# PCB_v2.net
KiCad netlist of a schematic drawn in EAGLE
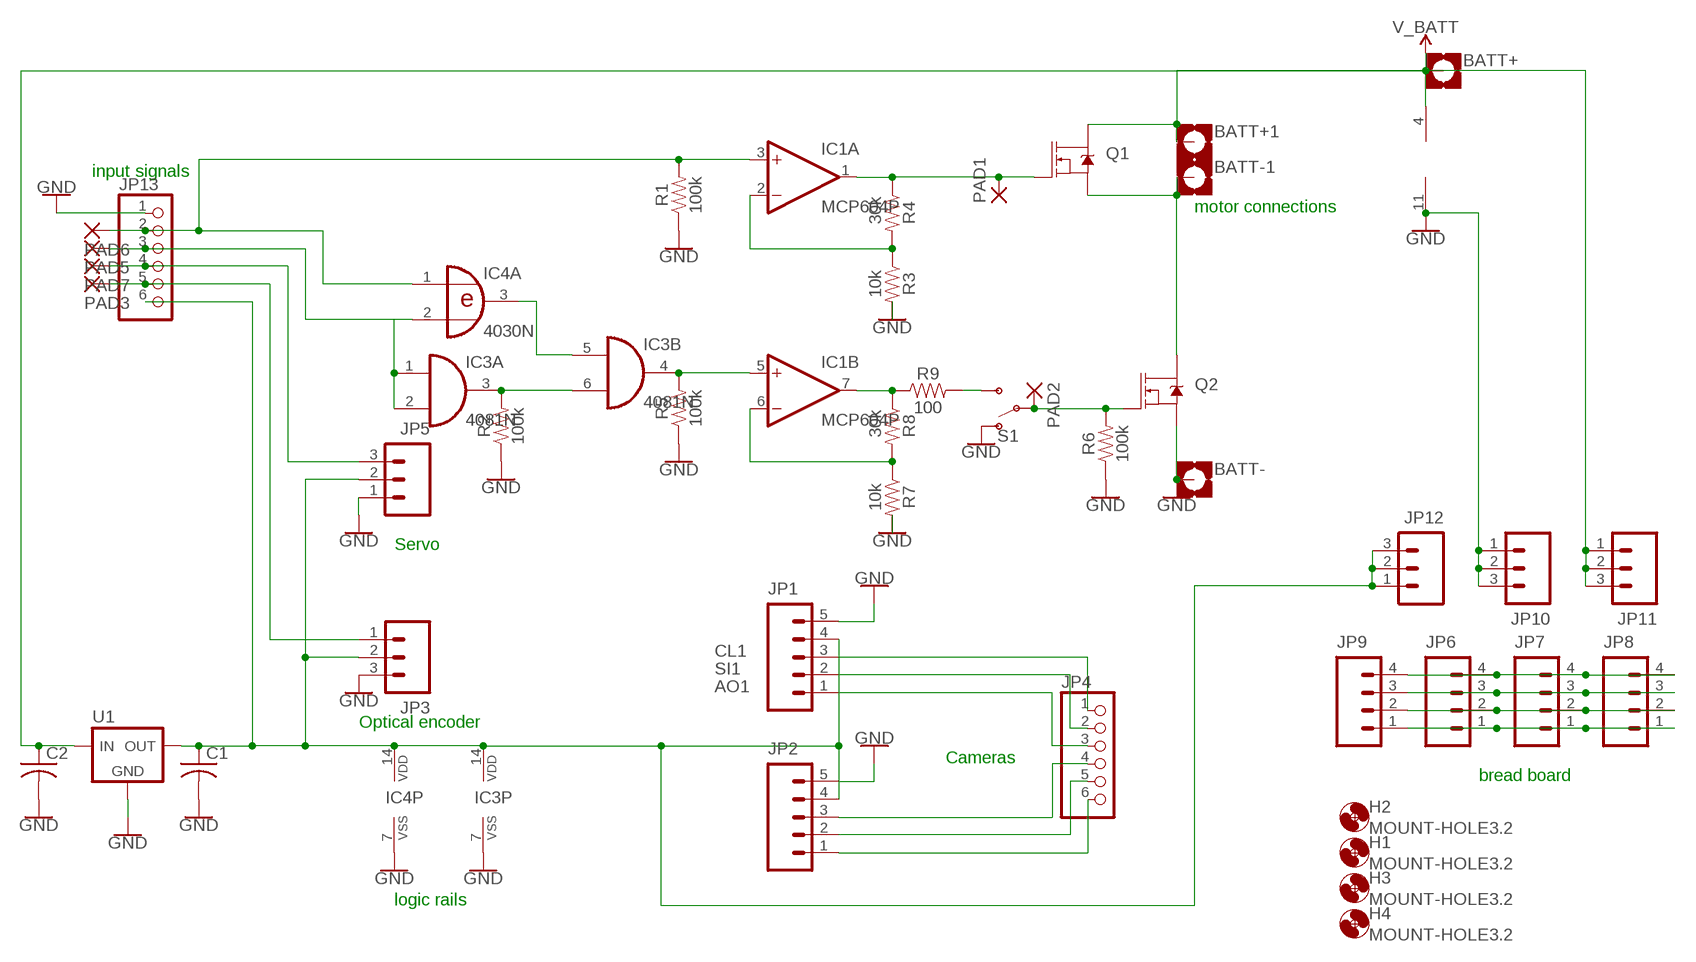
[diagram p0: schematic, sheet 1]

(export (version "E")
  (design (tool "Eeschema 10.0.6"))
  (components
    (comp (ref "BATT+")
      (value "MOUNT-PAD-SQUARE3.0")
      (footprint "eagle-import:3,0-PAD-SQUARE")
      (libsource (lib "eagle-import") (part "MOUNT-PAD-SQUARE3.0"))
    )
    (comp (ref "BATT+1")
      (value "MOUNT-PAD-SQUARE3.0")
      (footprint "eagle-import:3,0-PAD-SQUARE")
      (libsource (lib "eagle-import") (part "MOUNT-PAD-SQUARE3.0"))
    )
    (comp (ref "BATT-")
      (value "MOUNT-PAD-SQUARE3.0")
      (footprint "eagle-import:3,0-PAD-SQUARE")
      (libsource (lib "eagle-import") (part "MOUNT-PAD-SQUARE3.0"))
    )
    (comp (ref "BATT-1")
      (value "MOUNT-PAD-SQUARE3.0")
      (footprint "eagle-import:3,0-PAD-SQUARE")
      (libsource (lib "eagle-import") (part "MOUNT-PAD-SQUARE3.0"))
    )
    (comp (ref "C1")
      (value "C-075PTH")
      (footprint "eagle-import:C075")
      (libsource (lib "eagle-import") (part "C-075PTH"))
    )
    (comp (ref "C2")
      (value "C-075PTH")
      (footprint "eagle-import:C075")
      (libsource (lib "eagle-import") (part "C-075PTH"))
    )
    (comp (ref "H1")
      (value "MOUNT-HOLE3.2")
      (footprint "eagle-import:3,2")
      (libsource (lib "eagle-import") (part "MOUNT-HOLE3.2"))
    )
    (comp (ref "H2")
      (value "MOUNT-HOLE3.2")
      (footprint "eagle-import:3,2")
      (libsource (lib "eagle-import") (part "MOUNT-HOLE3.2"))
    )
    (comp (ref "H3")
      (value "MOUNT-HOLE3.2")
      (footprint "eagle-import:3,2")
      (libsource (lib "eagle-import") (part "MOUNT-HOLE3.2"))
    )
    (comp (ref "H4")
      (value "MOUNT-HOLE3.2")
      (footprint "eagle-import:3,2")
      (libsource (lib "eagle-import") (part "MOUNT-HOLE3.2"))
    )
    (comp (ref "IC1")
      (value "MCP604P")
      (footprint "eagle-import:DIL14")
      (libsource (lib "eagle-import") (part "MCP604P"))
    )
    (comp (ref "IC3")
      (value "4081N")
      (footprint "eagle-import:DIL14")
      (libsource (lib "eagle-import") (part "4081N"))
    )
    (comp (ref "IC4")
      (value "4030N")
      (footprint "eagle-import:DIL14")
      (libsource (lib "eagle-import") (part "4030N"))
    )
    (comp (ref "JP1")
      (value "M05PTH")
      (footprint "eagle-import:1X05")
      (libsource (lib "eagle-import") (part "M05PTH"))
    )
    (comp (ref "JP2")
      (value "M05PTH")
      (footprint "eagle-import:1X05")
      (libsource (lib "eagle-import") (part "M05PTH"))
    )
    (comp (ref "JP3")
      (value "M03PTH")
      (footprint "eagle-import:1X03")
      (libsource (lib "eagle-import") (part "M03PTH"))
    )
    (comp (ref "JP4")
      (value "PINHD-1X6")
      (footprint "eagle-import:1X06")
      (libsource (lib "eagle-import") (part "PINHD-1X6"))
    )
    (comp (ref "JP5")
      (value "M03PTH")
      (footprint "eagle-import:1X03")
      (libsource (lib "eagle-import") (part "M03PTH"))
    )
    (comp (ref "JP6")
      (value "M04PTH")
      (footprint "eagle-import:1X04")
      (libsource (lib "eagle-import") (part "M04PTH"))
    )
    (comp (ref "JP7")
      (value "M04PTH")
      (footprint "eagle-import:1X04")
      (libsource (lib "eagle-import") (part "M04PTH"))
    )
    (comp (ref "JP8")
      (value "M04PTH")
      (footprint "eagle-import:1X04")
      (libsource (lib "eagle-import") (part "M04PTH"))
    )
    (comp (ref "JP9")
      (value "M04PTH")
      (footprint "eagle-import:1X04")
      (libsource (lib "eagle-import") (part "M04PTH"))
    )
    (comp (ref "JP10")
      (value "M03PTH")
      (footprint "eagle-import:1X03")
      (libsource (lib "eagle-import") (part "M03PTH"))
    )
    (comp (ref "JP11")
      (value "M03PTH")
      (footprint "eagle-import:1X03")
      (libsource (lib "eagle-import") (part "M03PTH"))
    )
    (comp (ref "JP12")
      (value "M03PTH")
      (footprint "eagle-import:1X03")
      (libsource (lib "eagle-import") (part "M03PTH"))
    )
    (comp (ref "JP13")
      (value "PINHD-1X6")
      (footprint "eagle-import:1X06")
      (libsource (lib "eagle-import") (part "PINHD-1X6"))
    )
    (comp (ref "PAD1")
      (value "2,15/1,0")
      (footprint "eagle-import:2,15_1,0")
      (libsource (lib "eagle-import") (part "2,15/1,0"))
    )
    (comp (ref "PAD2")
      (value "2,15/1,0")
      (footprint "eagle-import:2,15_1,0")
      (libsource (lib "eagle-import") (part "2,15/1,0"))
    )
    (comp (ref "PAD3")
      (value "2,15/1,0")
      (footprint "eagle-import:2,15_1,0")
      (libsource (lib "eagle-import") (part "2,15/1,0"))
    )
    (comp (ref "PAD5")
      (value "2,15/1,0")
      (footprint "eagle-import:2,15_1,0")
      (libsource (lib "eagle-import") (part "2,15/1,0"))
    )
    (comp (ref "PAD6")
      (value "2,15/1,0")
      (footprint "eagle-import:2,15_1,0")
      (libsource (lib "eagle-import") (part "2,15/1,0"))
    )
    (comp (ref "PAD7")
      (value "2,15/1,0")
      (footprint "eagle-import:2,15_1,0")
      (libsource (lib "eagle-import") (part "2,15/1,0"))
    )
    (comp (ref "Q1")
      (value "MOSFET-NCH-FQP30N06L")
      (footprint "eagle-import:TO220V")
      (libsource (lib "eagle-import") (part "MOSFET-NCH-FQP30N06L"))
    )
    (comp (ref "Q2")
      (value "MOSFET-NCH-FQP30N06L")
      (footprint "eagle-import:TO220V")
      (libsource (lib "eagle-import") (part "MOSFET-NCH-FQP30N06L"))
    )
    (comp (ref "R1")
      (value "100k")
      (footprint "eagle-import:AXIAL-0.3")
      (libsource (lib "eagle-import") (part "10KOHM-HORIZ-1/4W-1%"))
    )
    (comp (ref "R2")
      (value "100k")
      (footprint "eagle-import:AXIAL-0.3")
      (libsource (lib "eagle-import") (part "10KOHM-HORIZ-1/4W-1%"))
    )
    (comp (ref "R3")
      (value "10k")
      (footprint "eagle-import:AXIAL-0.3")
      (libsource (lib "eagle-import") (part "10KOHM-HORIZ-1/4W-1%"))
    )
    (comp (ref "R4")
      (value "30k")
      (footprint "eagle-import:AXIAL-0.3")
      (libsource (lib "eagle-import") (part "RESISTORAXIAL-0.3"))
    )
    (comp (ref "R5")
      (value "100k")
      (footprint "eagle-import:AXIAL-0.3")
      (libsource (lib "eagle-import") (part "10KOHM-HORIZ-1/4W-1%"))
    )
    (comp (ref "R6")
      (value "100k")
      (footprint "eagle-import:AXIAL-0.3")
      (libsource (lib "eagle-import") (part "10KOHM-HORIZ-1/4W-1%"))
    )
    (comp (ref "R7")
      (value "10k")
      (footprint "eagle-import:AXIAL-0.3")
      (libsource (lib "eagle-import") (part "10KOHM-HORIZ-1/4W-1%"))
    )
    (comp (ref "R8")
      (value "30k")
      (footprint "eagle-import:AXIAL-0.3")
      (libsource (lib "eagle-import") (part "RESISTORAXIAL-0.3"))
    )
    (comp (ref "R9")
      (value "100")
      (footprint "eagle-import:AXIAL-0.3")
      (libsource (lib "eagle-import") (part "10KOHM-HORIZ-1/4W-1%"))
    )
    (comp (ref "S1")
      (value "SWITCH-SPDT-PTH-11.6X4.0MM-KIT")
      (footprint "eagle-import:SWITCH_SPDT_PTH_11.6X4.0MM_KIT")
      (libsource (lib "eagle-import") (part "SWITCH-SPDT-PTH-11.6X4.0MM-KIT"))
    )
    (comp (ref "U1")
      (value "78XX-TO220V")
      (footprint "eagle-import:TO220BV")
      (libsource (lib "eagle-import") (part "78XX-TO220V"))
    )
  )
  (nets
    (net (code "1") (name "/AO1") (class "Default")
      (node (ref "JP1") (pin "1") (pinfunction "1_1") (pintype "passive"))
      (node (ref "JP4") (pin "3") (pinfunction "3_3") (pintype "passive"))
    )
    (net (code "2") (name "/CL1") (class "Default")
      (node (ref "JP1") (pin "3") (pinfunction "3_3") (pintype "passive"))
      (node (ref "JP4") (pin "1") (pinfunction "1_1") (pintype "passive"))
    )
    (net (code "3") (name "/N$18") (class "Default")
      (node (ref "C1") (pin "1") (pinfunction "+_1") (pintype "passive"))
      (node (ref "IC3") (pin "14") (pinfunction "VDD_14") (pintype "power_in"))
      (node (ref "IC4") (pin "14") (pinfunction "VDD_14") (pintype "power_in"))
      (node (ref "JP1") (pin "4") (pinfunction "4_4") (pintype "passive"))
      (node (ref "JP12") (pin "1") (pinfunction "1_1") (pintype "passive"))
      (node (ref "JP12") (pin "2") (pinfunction "2_2") (pintype "passive"))
      (node (ref "JP12") (pin "3") (pinfunction "3_3") (pintype "passive"))
      (node (ref "JP13") (pin "6") (pinfunction "6_6") (pintype "passive"))
      (node (ref "JP2") (pin "4") (pinfunction "4_4") (pintype "passive"))
      (node (ref "JP3") (pin "2") (pinfunction "2_2") (pintype "passive"))
      (node (ref "JP5") (pin "2") (pinfunction "2_2") (pintype "passive"))
      (node (ref "U1") (pin "3") (pinfunction "VOUT_3") (pintype "power_in"))
    )
    (net (code "4") (name "/SI1") (class "Default")
      (node (ref "JP1") (pin "2") (pinfunction "2_2") (pintype "passive"))
      (node (ref "JP4") (pin "2") (pinfunction "2_2") (pintype "passive"))
    )
    (net (code "5") (name "GND") (class "Default")
      (node (ref "BATT-") (pin "B3,0") (pinfunction "MOUNT_B3,0") (pintype "passive"))
      (node (ref "C1") (pin "2") (pinfunction "-_2") (pintype "passive"))
      (node (ref "C2") (pin "2") (pinfunction "-_2") (pintype "passive"))
      (node (ref "IC1") (pin "11") (pinfunction "V-_11") (pintype "power_in"))
      (node (ref "IC3") (pin "7") (pinfunction "VSS_7") (pintype "power_in"))
      (node (ref "IC4") (pin "7") (pinfunction "VSS_7") (pintype "power_in"))
      (node (ref "JP1") (pin "5") (pinfunction "5_5") (pintype "passive"))
      (node (ref "JP10") (pin "1") (pinfunction "1_1") (pintype "passive"))
      (node (ref "JP10") (pin "2") (pinfunction "2_2") (pintype "passive"))
      (node (ref "JP10") (pin "3") (pinfunction "3_3") (pintype "passive"))
      (node (ref "JP13") (pin "1") (pinfunction "1_1") (pintype "passive"))
      (node (ref "JP2") (pin "5") (pinfunction "5_5") (pintype "passive"))
      (node (ref "JP3") (pin "3") (pinfunction "3_3") (pintype "passive"))
      (node (ref "JP5") (pin "1") (pinfunction "1_1") (pintype "passive"))
      (node (ref "Q2") (pin "3") (pinfunction "S_3") (pintype "bidirectional"))
      (node (ref "R1") (pin "P$1") (pinfunction "1_P$1") (pintype "passive"))
      (node (ref "R2") (pin "P$1") (pinfunction "1_P$1") (pintype "passive"))
      (node (ref "R3") (pin "P$2") (pinfunction "2_P$2") (pintype "passive"))
      (node (ref "R5") (pin "P$1") (pinfunction "1_P$1") (pintype "passive"))
      (node (ref "R6") (pin "P$1") (pinfunction "1_P$1") (pintype "passive"))
      (node (ref "R7") (pin "P$2") (pinfunction "2_P$2") (pintype "passive"))
      (node (ref "S1") (pin "1") (pinfunction "O_1") (pintype "passive"))
      (node (ref "U1") (pin "2") (pinfunction "GND_2") (pintype "power_in"))
    )
    (net (code "6") (name "Net-(BATT-1-MOUNT)") (class "Default")
      (node (ref "BATT-1") (pin "B3,0") (pinfunction "MOUNT_B3,0") (pintype "passive"))
      (node (ref "Q1") (pin "3") (pinfunction "S_3") (pintype "bidirectional"))
      (node (ref "Q2") (pin "2") (pinfunction "D_2") (pintype "bidirectional"))
    )
    (net (code "7") (name "Net-(IC1A-+IN)") (class "Default")
      (node (ref "IC1") (pin "3") (pinfunction "+IN_3") (pintype "input"))
      (node (ref "IC4") (pin "1") (pinfunction "I0_1") (pintype "input"))
      (node (ref "JP13") (pin "2") (pinfunction "2_2") (pintype "passive"))
      (node (ref "PAD6") (pin "1") (pinfunction "P_1") (pintype "passive"))
      (node (ref "R1") (pin "P$2") (pinfunction "2_P$2") (pintype "passive"))
    )
    (net (code "8") (name "Net-(IC1A--IN)") (class "Default")
      (node (ref "IC1") (pin "2") (pinfunction "-IN_2") (pintype "input"))
      (node (ref "R3") (pin "P$1") (pinfunction "1_P$1") (pintype "passive"))
      (node (ref "R4") (pin "P$2") (pinfunction "2_P$2") (pintype "passive"))
    )
    (net (code "9") (name "Net-(IC1A-OUT)") (class "Default")
      (node (ref "IC1") (pin "1") (pinfunction "OUT_1") (pintype "output"))
      (node (ref "PAD1") (pin "1") (pinfunction "P_1") (pintype "passive"))
      (node (ref "Q1") (pin "1") (pinfunction "G_1") (pintype "bidirectional"))
      (node (ref "R4") (pin "P$1") (pinfunction "1_P$1") (pintype "passive"))
    )
    (net (code "10") (name "Net-(IC1B-+IN)") (class "Default")
      (node (ref "IC1") (pin "5") (pinfunction "+IN_5") (pintype "input"))
      (node (ref "IC3") (pin "4") (pinfunction "O_4") (pintype "output"))
      (node (ref "R5") (pin "P$2") (pinfunction "2_P$2") (pintype "passive"))
    )
    (net (code "11") (name "Net-(IC1B--IN)") (class "Default")
      (node (ref "IC1") (pin "6") (pinfunction "-IN_6") (pintype "input"))
      (node (ref "R7") (pin "P$1") (pinfunction "1_P$1") (pintype "passive"))
      (node (ref "R8") (pin "P$2") (pinfunction "2_P$2") (pintype "passive"))
    )
    (net (code "12") (name "Net-(IC1B-OUT)") (class "Default")
      (node (ref "IC1") (pin "7") (pinfunction "OUT_7") (pintype "output"))
      (node (ref "R8") (pin "P$1") (pinfunction "1_P$1") (pintype "passive"))
      (node (ref "R9") (pin "P$1") (pinfunction "1_P$1") (pintype "passive"))
    )
    (net (code "13") (name "Net-(IC3A-I0)") (class "Default")
      (node (ref "IC3") (pin "1") (pinfunction "I0_1") (pintype "input"))
      (node (ref "IC3") (pin "2") (pinfunction "I1_2") (pintype "input"))
      (node (ref "IC4") (pin "2") (pinfunction "I1_2") (pintype "input"))
      (node (ref "JP13") (pin "3") (pinfunction "3_3") (pintype "passive"))
      (node (ref "PAD5") (pin "1") (pinfunction "P_1") (pintype "passive"))
    )
    (net (code "14") (name "Net-(IC3A-O)") (class "Default")
      (node (ref "IC3") (pin "3") (pinfunction "O_3") (pintype "output"))
      (node (ref "IC3") (pin "6") (pinfunction "I1_6") (pintype "input"))
      (node (ref "R2") (pin "P$2") (pinfunction "2_P$2") (pintype "passive"))
    )
    (net (code "15") (name "Net-(IC3B-I0)") (class "Default")
      (node (ref "IC3") (pin "5") (pinfunction "I0_5") (pintype "input"))
      (node (ref "IC4") (pin "3") (pinfunction "O_3") (pintype "output"))
    )
    (net (code "16") (name "Net-(JP2-Pad1)") (class "Default")
      (node (ref "JP2") (pin "1") (pinfunction "1_1") (pintype "passive"))
      (node (ref "JP4") (pin "6") (pinfunction "6_6") (pintype "passive"))
    )
    (net (code "17") (name "Net-(JP2-Pad2)") (class "Default")
      (node (ref "JP2") (pin "2") (pinfunction "2_2") (pintype "passive"))
      (node (ref "JP4") (pin "5") (pinfunction "5_5") (pintype "passive"))
    )
    (net (code "18") (name "Net-(JP2-Pad3)") (class "Default")
      (node (ref "JP2") (pin "3") (pinfunction "3_3") (pintype "passive"))
      (node (ref "JP4") (pin "4") (pinfunction "4_4") (pintype "passive"))
    )
    (net (code "19") (name "Net-(JP6-Pad1)") (class "Default")
      (node (ref "JP6") (pin "1") (pinfunction "1_1") (pintype "passive"))
      (node (ref "JP7") (pin "1") (pinfunction "1_1") (pintype "passive"))
      (node (ref "JP8") (pin "1") (pinfunction "1_1") (pintype "passive"))
      (node (ref "JP9") (pin "1") (pinfunction "1_1") (pintype "passive"))
    )
    (net (code "20") (name "Net-(JP6-Pad2)") (class "Default")
      (node (ref "JP6") (pin "2") (pinfunction "2_2") (pintype "passive"))
      (node (ref "JP7") (pin "2") (pinfunction "2_2") (pintype "passive"))
      (node (ref "JP8") (pin "2") (pinfunction "2_2") (pintype "passive"))
      (node (ref "JP9") (pin "2") (pinfunction "2_2") (pintype "passive"))
    )
    (net (code "21") (name "Net-(JP6-Pad3)") (class "Default")
      (node (ref "JP6") (pin "3") (pinfunction "3_3") (pintype "passive"))
      (node (ref "JP7") (pin "3") (pinfunction "3_3") (pintype "passive"))
      (node (ref "JP8") (pin "3") (pinfunction "3_3") (pintype "passive"))
      (node (ref "JP9") (pin "3") (pinfunction "3_3") (pintype "passive"))
    )
    (net (code "22") (name "Net-(JP6-Pad4)") (class "Default")
      (node (ref "JP6") (pin "4") (pinfunction "4_4") (pintype "passive"))
      (node (ref "JP7") (pin "4") (pinfunction "4_4") (pintype "passive"))
      (node (ref "JP8") (pin "4") (pinfunction "4_4") (pintype "passive"))
      (node (ref "JP9") (pin "4") (pinfunction "4_4") (pintype "passive"))
    )
    (net (code "23") (name "Net-(PAD2-P)") (class "Default")
      (node (ref "PAD2") (pin "1") (pinfunction "P_1") (pintype "passive"))
      (node (ref "Q2") (pin "1") (pinfunction "G_1") (pintype "bidirectional"))
      (node (ref "R6") (pin "P$2") (pinfunction "2_P$2") (pintype "passive"))
      (node (ref "S1") (pin "2") (pinfunction "P_2") (pintype "passive"))
    )
    (net (code "24") (name "Net-(PAD3-P)") (class "Default")
      (node (ref "JP13") (pin "5") (pinfunction "5_5") (pintype "passive"))
      (node (ref "JP3") (pin "1") (pinfunction "1_1") (pintype "passive"))
      (node (ref "PAD3") (pin "1") (pinfunction "P_1") (pintype "passive"))
    )
    (net (code "25") (name "Net-(PAD7-P)") (class "Default")
      (node (ref "JP13") (pin "4") (pinfunction "4_4") (pintype "passive"))
      (node (ref "JP5") (pin "3") (pinfunction "3_3") (pintype "passive"))
      (node (ref "PAD7") (pin "1") (pinfunction "P_1") (pintype "passive"))
    )
    (net (code "26") (name "Net-(R9-2)") (class "Default")
      (node (ref "R9") (pin "P$2") (pinfunction "2_P$2") (pintype "passive"))
      (node (ref "S1") (pin "3") (pinfunction "S_3") (pintype "passive"))
    )
    (net (code "27") (name "V_BATT") (class "Default")
      (node (ref "BATT+") (pin "B3,0") (pinfunction "MOUNT_B3,0") (pintype "passive"))
      (node (ref "BATT+1") (pin "B3,0") (pinfunction "MOUNT_B3,0") (pintype "passive"))
      (node (ref "C2") (pin "1") (pinfunction "+_1") (pintype "passive"))
      (node (ref "IC1") (pin "4") (pinfunction "V+_4") (pintype "power_in"))
      (node (ref "JP11") (pin "1") (pinfunction "1_1") (pintype "passive"))
      (node (ref "JP11") (pin "2") (pinfunction "2_2") (pintype "passive"))
      (node (ref "JP11") (pin "3") (pinfunction "3_3") (pintype "passive"))
      (node (ref "Q1") (pin "2") (pinfunction "D_2") (pintype "bidirectional"))
      (node (ref "U1") (pin "1") (pinfunction "VIN_1") (pintype "power_in"))
    )
  )
)
